# USB.net
KiCad netlist of a schematic drawn in Altium Designer
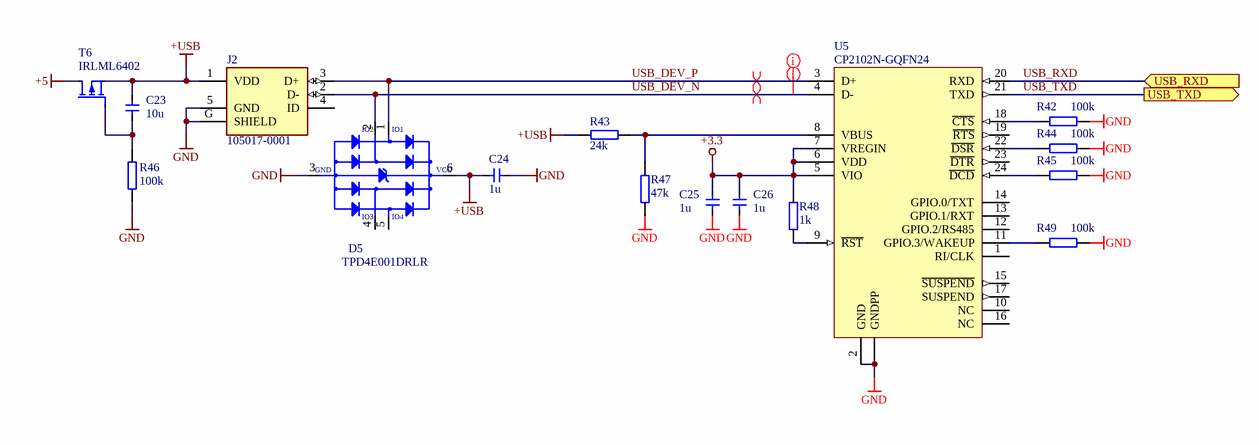
[diagram p0: USB.SchDoc]

(export (version "E")
  (design (tool "Eeschema 10.0.6"))
  (components
    (comp (ref "C23")
      (value "10u")
      (footprint "C0805")
      (description "C; capacitor")
      (libsource (lib "SONEL_all") (part "C"))
    )
    (comp (ref "C24")
      (value "1u")
      (footprint "C0805")
      (description "C; capacitor")
      (libsource (lib "SONEL_all") (part "C"))
    )
    (comp (ref "C25")
      (value "1u")
      (footprint "C0805")
      (description "capacitor")
      (libsource (lib "SONEL_all") (part "C"))
    )
    (comp (ref "C26")
      (value "1u")
      (footprint "C0805")
      (description "capacitor")
      (libsource (lib "SONEL_all") (part "C"))
    )
    (comp (ref "D5")
      (value "TPD4E001DRLR")
      (footprint "DRL_R-PDSO-N6")
      (description "D_; ESD Protection")
      (libsource (lib "SONEL_all") (part "TPD4E001DRLR"))
    )
    (comp (ref "J2")
      (value "105017-0001")
      (footprint "MOLEX_105017-0001")
      (description "CON; USB; micro B USB 2.0 Receptacle Connector 5 Position Surface Mount, Right Angle; Through Hole")
      (libsource (lib "sch") (part "105017-0001"))
    )
    (comp (ref "R42")
      (value "100k")
      (footprint "R0805")
      (description "resistor")
      (libsource (lib "SONEL_all") (part "R"))
    )
    (comp (ref "R43")
      (value "24k")
      (footprint "R0805")
      (description "resistor")
      (libsource (lib "SONEL_all") (part "R"))
    )
    (comp (ref "R44")
      (value "100k")
      (footprint "R0805")
      (description "resistor")
      (libsource (lib "SONEL_all") (part "R"))
    )
    (comp (ref "R45")
      (value "100k")
      (footprint "R0805")
      (description "resistor")
      (libsource (lib "SONEL_all") (part "R"))
    )
    (comp (ref "R46")
      (value "100k")
      (footprint "R0805")
      (description "R; resistor")
      (libsource (lib "SONEL_all") (part "R"))
    )
    (comp (ref "R47")
      (value "47k")
      (footprint "R0805")
      (description "resistor")
      (libsource (lib "SONEL_all") (part "R"))
    )
    (comp (ref "R48")
      (value "1k")
      (footprint "R0805")
      (description "resistor")
      (libsource (lib "SONEL_all") (part "R"))
    )
    (comp (ref "R49")
      (value "100k")
      (footprint "R0805")
      (description "resistor")
      (libsource (lib "SONEL_all") (part "R"))
    )
    (comp (ref "T6")
      (value "IRLML6402")
      (footprint "MICRO3")
      (description "T_M_P; P-Channel MOSFET")
      (libsource (lib "SONEL_all") (part "IRLML6402"))
    )
    (comp (ref "U5")
      (value "CP2102N-GQFN24")
      (footprint "RGE_S-PVQFN-N24-B")
      (description "USB-to-UART (USB 2.0 Full-Speed) Bridge Controller")
      (libsource (lib "SONEL_all") (part "CP2102N-xxx-GQFN24"))
    )
  )
  (nets
    (net (code "1") (name "+3.3") (class "Default")
      (node (ref "C25") (pin "2") (pintype "passive"))
      (node (ref "C26") (pin "1") (pintype "passive"))
      (node (ref "R48") (pin "1") (pintype "passive"))
      (node (ref "U5") (pin "5") (pinfunction "VIO_5") (pintype "power_in"))
      (node (ref "U5") (pin "6") (pinfunction "VDD_6") (pintype "power_in"))
      (node (ref "U5") (pin "7") (pinfunction "VREGIN_7") (pintype "power_in"))
    )
    (net (code "2") (name "+5") (class "Default")
      (node (ref "T6") (pin "D") (pinfunction "D_D") (pintype "passive"))
    )
    (net (code "3") (name "+USB") (class "Default")
      (node (ref "C23") (pin "2") (pintype "passive"))
      (node (ref "C24") (pin "2") (pintype "passive"))
      (node (ref "D5") (pin "6") (pintype "power_in"))
      (node (ref "J2") (pin "1") (pinfunction "VDD_1") (pintype "power_in"))
      (node (ref "R43") (pin "1") (pintype "passive"))
      (node (ref "T6") (pin "S") (pinfunction "S_S") (pintype "passive"))
    )
    (net (code "4") (name "/USB_DEV_N") (class "Default")
      (node (ref "D5") (pin "2") (pintype "passive"))
      (node (ref "J2") (pin "2") (pinfunction "D-_2") (pintype "bidirectional"))
      (node (ref "U5") (pin "4") (pinfunction "D-_4") (pintype "passive"))
    )
    (net (code "5") (name "/USB_DEV_P") (class "Default")
      (node (ref "D5") (pin "1") (pintype "passive"))
      (node (ref "J2") (pin "3") (pinfunction "D+_3") (pintype "bidirectional"))
      (node (ref "U5") (pin "3") (pinfunction "D+_3") (pintype "passive"))
    )
    (net (code "6") (name "/USB_RXD") (class "Default")
      (node (ref "U5") (pin "20") (pinfunction "RXD_20") (pintype "input"))
    )
    (net (code "7") (name "/USB_TXD") (class "Default")
      (node (ref "U5") (pin "21") (pinfunction "TXD_21") (pintype "output"))
    )
    (net (code "8") (name "GND") (class "Default")
      (node (ref "C24") (pin "1") (pintype "passive"))
      (node (ref "C25") (pin "1") (pintype "passive"))
      (node (ref "C26") (pin "2") (pintype "passive"))
      (node (ref "D5") (pin "3") (pintype "power_in"))
      (node (ref "J2") (pin "5") (pinfunction "GND_5") (pintype "power_in"))
      (node (ref "J2") (pin "G") (pinfunction "SHIELD_G") (pintype "power_in"))
      (node (ref "R42") (pin "1") (pintype "passive"))
      (node (ref "R44") (pin "1") (pintype "passive"))
      (node (ref "R45") (pin "1") (pintype "passive"))
      (node (ref "R46") (pin "1") (pintype "passive"))
      (node (ref "R47") (pin "1") (pintype "passive"))
      (node (ref "R49") (pin "1") (pintype "passive"))
      (node (ref "U5") (pin "0") (pinfunction "GNDPP_0") (pintype "power_in"))
      (node (ref "U5") (pin "2") (pinfunction "GND_2") (pintype "power_in"))
    )
    (net (code "9") (name "Net-(C23-Pad1)") (class "Default")
      (node (ref "C23") (pin "1") (pintype "passive"))
      (node (ref "R46") (pin "2") (pintype "passive"))
      (node (ref "T6") (pin "G") (pinfunction "G_G") (pintype "passive"))
    )
    (net (code "10") (name "Net-(U5-GPIO.3{slash}WAKEUP)") (class "Default")
      (node (ref "R49") (pin "2") (pintype "passive"))
      (node (ref "U5") (pin "11") (pinfunction "GPIO.3/WAKEUP_11") (pintype "passive"))
    )
    (net (code "11") (name "Net-(U5-VBUS)") (class "Default")
      (node (ref "R43") (pin "2") (pintype "passive"))
      (node (ref "R47") (pin "2") (pintype "passive"))
      (node (ref "U5") (pin "8") (pinfunction "VBUS_8") (pintype "passive"))
    )
    (net (code "12") (name "Net-(U5-~{CTS})") (class "Default")
      (node (ref "R42") (pin "2") (pintype "passive"))
      (node (ref "U5") (pin "18") (pinfunction "~{CTS}_18") (pintype "input"))
    )
    (net (code "13") (name "Net-(U5-~{DCD})") (class "Default")
      (node (ref "R45") (pin "2") (pintype "passive"))
      (node (ref "U5") (pin "24") (pinfunction "~{DCD}_24") (pintype "input"))
    )
    (net (code "14") (name "Net-(U5-~{DSR})") (class "Default")
      (node (ref "R44") (pin "2") (pintype "passive"))
      (node (ref "U5") (pin "22") (pinfunction "~{DSR}_22") (pintype "input"))
    )
    (net (code "15") (name "Net-(U5-~{RST})") (class "Default")
      (node (ref "R48") (pin "2") (pintype "passive"))
      (node (ref "U5") (pin "9") (pinfunction "~{RST}_9") (pintype "input"))
    )
    (net (code "16") (name "unconnected-(D5-Pad4)") (class "Default")
      (node (ref "D5") (pin "4") (pintype "passive"))
    )
    (net (code "17") (name "unconnected-(D5-Pad5)") (class "Default")
      (node (ref "D5") (pin "5") (pintype "passive"))
    )
    (net (code "18") (name "unconnected-(J2-ID-Pad4)") (class "Default")
      (node (ref "J2") (pin "4") (pinfunction "ID_4") (pintype "passive"))
    )
    (net (code "19") (name "unconnected-(U5-GPIO.0{slash}TXT-Pad14)") (class "Default")
      (node (ref "U5") (pin "14") (pinfunction "GPIO.0/TXT_14") (pintype "passive"))
    )
    (net (code "20") (name "unconnected-(U5-GPIO.1{slash}RXT-Pad13)") (class "Default")
      (node (ref "U5") (pin "13") (pinfunction "GPIO.1/RXT_13") (pintype "passive"))
    )
    (net (code "21") (name "unconnected-(U5-GPIO.2{slash}RS485-Pad12)") (class "Default")
      (node (ref "U5") (pin "12") (pinfunction "GPIO.2/RS485_12") (pintype "passive"))
    )
    (net (code "22") (name "unconnected-(U5-NC-Pad10)") (class "Default")
      (node (ref "U5") (pin "10") (pinfunction "NC_10") (pintype "passive"))
    )
    (net (code "23") (name "unconnected-(U5-NC-Pad16)") (class "Default")
      (node (ref "U5") (pin "16") (pinfunction "NC_16") (pintype "passive"))
    )
    (net (code "24") (name "unconnected-(U5-RI{slash}CLK-Pad1)") (class "Default")
      (node (ref "U5") (pin "1") (pinfunction "RI/CLK_1") (pintype "passive"))
    )
    (net (code "25") (name "unconnected-(U5-SUSPEND-Pad17)") (class "Default")
      (node (ref "U5") (pin "17") (pinfunction "SUSPEND_17") (pintype "output"))
    )
    (net (code "26") (name "unconnected-(U5-~{DTR}-Pad23)") (class "Default")
      (node (ref "U5") (pin "23") (pinfunction "~{DTR}_23") (pintype "output"))
    )
    (net (code "27") (name "unconnected-(U5-~{RTS}-Pad19)") (class "Default")
      (node (ref "U5") (pin "19") (pinfunction "~{RTS}_19") (pintype "output"))
    )
    (net (code "28") (name "unconnected-(U5-~{SUSPEND}-Pad15)") (class "Default")
      (node (ref "U5") (pin "15") (pinfunction "~{SUSPEND}_15") (pintype "output"))
    )
  )
)
